# Sheet1.net
KiCad netlist of a schematic drawn in Altium Designer
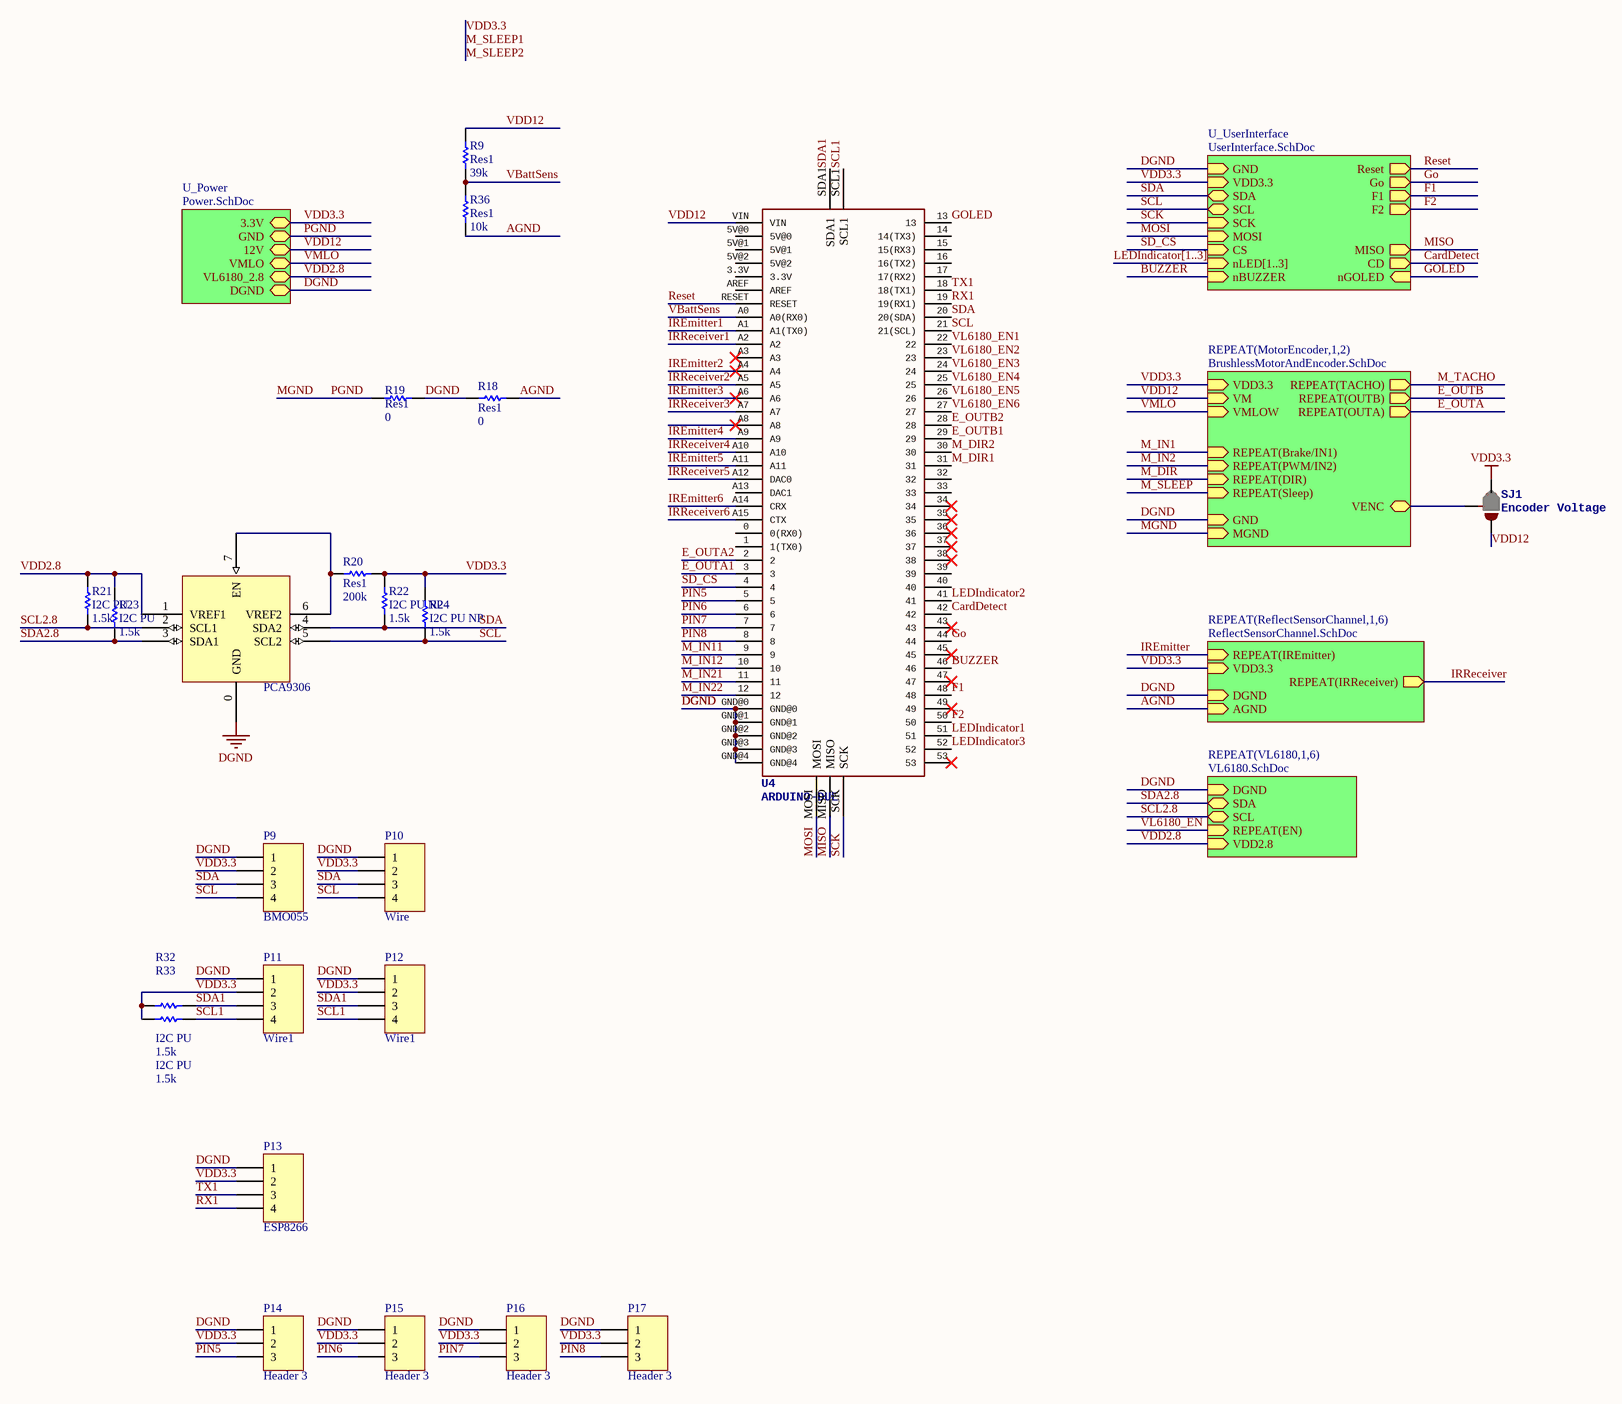
[diagram p0: Sheet1.SchDoc]

(export (version "E")
  (design (tool "Eeschema 10.0.6"))
  (components
    (comp (ref "P9")
      (value "BMO055")
      (footprint "PH_4_PTH")
      (description "Header, 4-Pin")
      (fields (field (name "PUBLISHER") "Altium Limited"))
      (libsource (lib "SmartMouse2016") (part "Header 4"))
    )
    (comp (ref "P10")
      (value "Wire")
      (footprint "PH_4_PTH")
      (description "Header, 4-Pin")
      (fields (field (name "PUBLISHER") "Altium Limited"))
      (libsource (lib "SmartMouse2016") (part "Header 4"))
    )
    (comp (ref "P11")
      (value "Wire1")
      (footprint "PH_4_PTH")
      (description "Header, 4-Pin")
      (fields (field (name "PUBLISHER") "Altium Limited"))
      (libsource (lib "SmartMouse2016") (part "Header 4"))
    )
    (comp (ref "P12")
      (value "Wire1")
      (footprint "PH_4_PTH")
      (description "Header, 4-Pin")
      (fields (field (name "PUBLISHER") "Altium Limited"))
      (libsource (lib "SmartMouse2016") (part "Header 4"))
    )
    (comp (ref "P13")
      (value "ESP8266")
      (footprint "PH_4_PTH")
      (description "Header, 4-Pin")
      (fields (field (name "PUBLISHER") "Altium Limited"))
      (libsource (lib "SmartMouse2016") (part "Header 4"))
    )
    (comp (ref "P14")
      (value "Header 3")
      (footprint "HDR1X3")
      (description "Header, 3-Pin")
      (fields (field (name "PUBLISHER") "Altium Limited"))
      (libsource (lib "Miscellaneous Connectors") (part "Header 3"))
    )
    (comp (ref "P15")
      (value "Header 3")
      (footprint "HDR1X3")
      (description "Header, 3-Pin")
      (fields (field (name "PUBLISHER") "Altium Limited"))
      (libsource (lib "Miscellaneous Connectors") (part "Header 3"))
    )
    (comp (ref "P16")
      (value "Header 3")
      (footprint "HDR1X3")
      (description "Header, 3-Pin")
      (fields (field (name "PUBLISHER") "Altium Limited"))
      (libsource (lib "Miscellaneous Connectors") (part "Header 3"))
    )
    (comp (ref "P17")
      (value "Header 3")
      (footprint "HDR1X3")
      (description "Header, 3-Pin")
      (fields (field (name "PUBLISHER") "Altium Limited"))
      (libsource (lib "Miscellaneous Connectors") (part "Header 3"))
    )
    (comp (ref "PCA1")
      (value "PCA9306")
      (footprint "SOIC_E200_8")
      (description "I2C shifting voltage")
      (libsource (lib "patricklib") (part "Component_1_1"))
    )
    (comp (ref "R9")
      (value "Res1")
      (footprint "RES_0805")
      (description "Resistor")
      (fields (field (name "ALTIUM_VALUE") "39k") (field (name "PUBLISHER") "Altium Limited"))
      (libsource (lib "SmartMouse2016") (part "Res1"))
    )
    (comp (ref "R18")
      (value "Res1")
      (footprint "RES_0805")
      (description "Resistor")
      (fields (field (name "ALTIUM_VALUE") "0") (field (name "PUBLISHER") "Altium Limited"))
      (libsource (lib "SmartMouse2016") (part "Res1"))
    )
    (comp (ref "R19")
      (value "Res1")
      (footprint "RES_0805")
      (description "Resistor")
      (fields (field (name "ALTIUM_VALUE") "0") (field (name "PUBLISHER") "Altium Limited"))
      (libsource (lib "SmartMouse2016") (part "Res1"))
    )
    (comp (ref "R20")
      (value "Res1")
      (footprint "RES_0805")
      (description "Resistor")
      (fields (field (name "ALTIUM_VALUE") "200k") (field (name "PUBLISHER") "Altium Limited"))
      (libsource (lib "SmartMouse2016") (part "Res1"))
    )
    (comp (ref "R21")
      (value "I2C PU")
      (footprint "RES_0805")
      (description "Resistor")
      (fields (field (name "ALTIUM_VALUE") "1.5k") (field (name "PUBLISHER") "Altium Limited"))
      (libsource (lib "SmartMouse2016") (part "Res1"))
    )
    (comp (ref "R22")
      (value "I2C PU NP")
      (footprint "RES_0805")
      (description "Resistor")
      (fields (field (name "ALTIUM_VALUE") "1.5k") (field (name "PUBLISHER") "Altium Limited"))
      (libsource (lib "SmartMouse2016") (part "Res1"))
    )
    (comp (ref "R23")
      (value "I2C PU")
      (footprint "RES_0805")
      (description "Resistor")
      (fields (field (name "ALTIUM_VALUE") "1.5k") (field (name "PUBLISHER") "Altium Limited"))
      (libsource (lib "SmartMouse2016") (part "Res1"))
    )
    (comp (ref "R24")
      (value "I2C PU NP")
      (footprint "RES_0805")
      (description "Resistor")
      (fields (field (name "ALTIUM_VALUE") "1.5k") (field (name "PUBLISHER") "Altium Limited"))
      (libsource (lib "SmartMouse2016") (part "Res1"))
    )
    (comp (ref "R32")
      (value "I2C PU")
      (footprint "RES_0805")
      (description "Resistor")
      (fields (field (name "ALTIUM_VALUE") "1.5k") (field (name "PUBLISHER") "Altium Limited"))
      (libsource (lib "SmartMouse2016") (part "Res1"))
    )
    (comp (ref "R33")
      (value "I2C PU")
      (footprint "RES_0805")
      (description "Resistor")
      (fields (field (name "ALTIUM_VALUE") "1.5k") (field (name "PUBLISHER") "Altium Limited"))
      (libsource (lib "SmartMouse2016") (part "Res1"))
    )
    (comp (ref "R36")
      (value "Res1")
      (footprint "RES_0805")
      (description "Resistor")
      (fields (field (name "ALTIUM_VALUE") "10k") (field (name "PUBLISHER") "Altium Limited"))
      (libsource (lib "SmartMouse2016") (part "Res1"))
    )
    (comp (ref "SJ1")
      (value "Encoder Voltage")
      (footprint "PAD-JUMPER-3-2OF3_NC_BY_PASTE_YES_SILK_FULL_BOX")
      (libsource (lib "SparkFun-Passives") (part "JUMPER-PAD-3-2OF3_NC_BY_PASTE"))
    )
    (comp (ref "U4")
      (value "ARDUINO-DUE")
      (footprint "ARDUINO_DUE")
      (libsource (lib "Robotics") (part "ARDUINO-DUE"))
    )
  )
  (nets
    (net (code "1") (name "/AGND") (class "Default")
      (node (ref "R18") (pin "2") (pinfunction "2_2") (pintype "passive"))
      (node (ref "R36") (pin "1") (pinfunction "1_1") (pintype "passive"))
    )
    (net (code "2") (name "/BUZZER") (class "Default")
      (node (ref "U4") (pin "46") (pinfunction "46_46") (pintype "passive"))
    )
    (net (code "3") (name "/CardDetect") (class "Default")
      (node (ref "U4") (pin "42") (pinfunction "42_42") (pintype "passive"))
    )
    (net (code "5") (name "/E_OUTA1") (class "Default")
      (node (ref "U4") (pin "3") (pinfunction "3_3") (pintype "passive"))
    )
    (net (code "6") (name "/E_OUTA2") (class "Default")
      (node (ref "U4") (pin "2") (pinfunction "2_2") (pintype "passive"))
    )
    (net (code "8") (name "/E_OUTB1") (class "Default")
      (node (ref "U4") (pin "29") (pinfunction "29_29") (pintype "passive"))
    )
    (net (code "9") (name "/E_OUTB2") (class "Default")
      (node (ref "U4") (pin "28") (pinfunction "28_28") (pintype "passive"))
    )
    (net (code "10") (name "/F1") (class "Default")
      (node (ref "U4") (pin "48") (pinfunction "48_48") (pintype "passive"))
    )
    (net (code "11") (name "/F2") (class "Default")
      (node (ref "U4") (pin "50") (pinfunction "50_50") (pintype "passive"))
    )
    (net (code "12") (name "/GOLED") (class "Default")
      (node (ref "U4") (pin "13") (pinfunction "13_13") (pintype "passive"))
    )
    (net (code "13") (name "/Go") (class "Default")
      (node (ref "U4") (pin "44") (pinfunction "44_44") (pintype "passive"))
    )
    (net (code "15") (name "/IREmitter1") (class "Default")
      (node (ref "U4") (pin "A1") (pinfunction "A1(TX0)_A1") (pintype "passive"))
    )
    (net (code "16") (name "/IREmitter2") (class "Default")
      (node (ref "U4") (pin "A4") (pinfunction "A4_A4") (pintype "passive+no_connect"))
    )
    (net (code "17") (name "/IREmitter3") (class "Default")
      (node (ref "U4") (pin "A6") (pinfunction "A6_A6") (pintype "passive+no_connect"))
    )
    (net (code "18") (name "/IREmitter4") (class "Default")
      (node (ref "U4") (pin "A9") (pinfunction "A9_A9") (pintype "passive"))
    )
    (net (code "19") (name "/IREmitter5") (class "Default")
      (node (ref "U4") (pin "A11") (pinfunction "A11_A11") (pintype "passive"))
    )
    (net (code "20") (name "/IREmitter6") (class "Default")
      (node (ref "U4") (pin "A14") (pinfunction "CRX_A14") (pintype "passive"))
    )
    (net (code "22") (name "/IRReceiver1") (class "Default")
      (node (ref "U4") (pin "A2") (pinfunction "A2_A2") (pintype "passive"))
    )
    (net (code "23") (name "/IRReceiver2") (class "Default")
      (node (ref "U4") (pin "A5") (pinfunction "A5_A5") (pintype "passive"))
    )
    (net (code "24") (name "/IRReceiver3") (class "Default")
      (node (ref "U4") (pin "A7") (pinfunction "A7_A7") (pintype "passive"))
    )
    (net (code "25") (name "/IRReceiver4") (class "Default")
      (node (ref "U4") (pin "A10") (pinfunction "A10_A10") (pintype "passive"))
    )
    (net (code "26") (name "/IRReceiver5") (class "Default")
      (node (ref "U4") (pin "A12") (pinfunction "DAC0_A12") (pintype "passive"))
    )
    (net (code "27") (name "/IRReceiver6") (class "Default")
      (node (ref "U4") (pin "A15") (pinfunction "CTX_A15") (pintype "passive"))
    )
    (net (code "28") (name "/LEDIndicator1") (class "Default")
      (node (ref "U4") (pin "51") (pinfunction "51_51") (pintype "passive"))
    )
    (net (code "29") (name "/LEDIndicator2") (class "Default")
      (node (ref "U4") (pin "41") (pinfunction "41_41") (pintype "passive"))
    )
    (net (code "30") (name "/LEDIndicator3") (class "Default")
      (node (ref "U4") (pin "52") (pinfunction "52_52") (pintype "passive"))
    )
    (net (code "32") (name "/MGND") (class "Default")
      (node (ref "R19") (pin "1") (pinfunction "1_1") (pintype "passive"))
    )
    (net (code "33") (name "/MISO") (class "Default")
      (node (ref "U4") (pin "MISO") (pinfunction "MISO_MISO") (pintype "passive"))
    )
    (net (code "34") (name "/MOSI") (class "Default")
      (node (ref "U4") (pin "MOSI") (pinfunction "MOSI_MOSI") (pintype "passive"))
    )
    (net (code "36") (name "/M_DIR1") (class "Default")
      (node (ref "U4") (pin "31") (pinfunction "31_31") (pintype "passive"))
    )
    (net (code "37") (name "/M_DIR2") (class "Default")
      (node (ref "U4") (pin "30") (pinfunction "30_30") (pintype "passive"))
    )
    (net (code "40") (name "/M_IN11") (class "Default")
      (node (ref "U4") (pin "9") (pinfunction "9_9") (pintype "passive"))
    )
    (net (code "41") (name "/M_IN12") (class "Default")
      (node (ref "U4") (pin "10") (pinfunction "10_10") (pintype "passive"))
    )
    (net (code "42") (name "/M_IN21") (class "Default")
      (node (ref "U4") (pin "11") (pinfunction "11_11") (pintype "passive"))
    )
    (net (code "43") (name "/M_IN22") (class "Default")
      (node (ref "U4") (pin "12") (pinfunction "12_12") (pintype "passive"))
    )
    (net (code "46") (name "/PIN5") (class "Default")
      (node (ref "P14") (pin "3") (pinfunction "3_3") (pintype "passive"))
      (node (ref "U4") (pin "5") (pinfunction "5_5") (pintype "passive"))
    )
    (net (code "47") (name "/PIN6") (class "Default")
      (node (ref "P15") (pin "3") (pinfunction "3_3") (pintype "passive"))
      (node (ref "U4") (pin "6") (pinfunction "6_6") (pintype "passive"))
    )
    (net (code "48") (name "/PIN7") (class "Default")
      (node (ref "P16") (pin "3") (pinfunction "3_3") (pintype "passive"))
      (node (ref "U4") (pin "7") (pinfunction "7_7") (pintype "passive"))
    )
    (net (code "49") (name "/PIN8") (class "Default")
      (node (ref "P17") (pin "3") (pinfunction "3_3") (pintype "passive"))
      (node (ref "U4") (pin "8") (pinfunction "8_8") (pintype "passive"))
    )
    (net (code "50") (name "/RX1") (class "Default")
      (node (ref "P13") (pin "4") (pinfunction "4_4") (pintype "passive"))
      (node (ref "U4") (pin "19") (pinfunction "19(RX1)_19") (pintype "passive"))
    )
    (net (code "51") (name "/Reset") (class "Default")
      (node (ref "U4") (pin "RESET") (pinfunction "RESET_RESET") (pintype "passive"))
    )
    (net (code "52") (name "/SCK") (class "Default")
      (node (ref "U4") (pin "SCK") (pinfunction "SCK_SCK") (pintype "passive"))
    )
    (net (code "53") (name "/SCL") (class "Default")
      (node (ref "P10") (pin "4") (pinfunction "4_4") (pintype "passive"))
      (node (ref "P9") (pin "4") (pinfunction "4_4") (pintype "passive"))
      (node (ref "PCA1") (pin "5") (pinfunction "SCL2_5") (pintype "bidirectional"))
      (node (ref "R24") (pin "1") (pinfunction "1_1") (pintype "passive"))
      (node (ref "U4") (pin "21") (pinfunction "21(SCL)_21") (pintype "passive"))
    )
    (net (code "54") (name "/SCL1") (class "Default")
      (node (ref "P11") (pin "4") (pinfunction "4_4") (pintype "passive"))
      (node (ref "P12") (pin "4") (pinfunction "4_4") (pintype "passive"))
      (node (ref "R33") (pin "2") (pinfunction "2_2") (pintype "passive"))
      (node (ref "U4") (pin "SCL1") (pinfunction "SCL1_SCL1") (pintype "passive"))
    )
    (net (code "55") (name "/SCL2.8") (class "Default")
      (node (ref "PCA1") (pin "2") (pinfunction "SCL1_2") (pintype "bidirectional"))
      (node (ref "R21") (pin "1") (pinfunction "1_1") (pintype "passive"))
    )
    (net (code "56") (name "/SDA") (class "Default")
      (node (ref "P10") (pin "3") (pinfunction "3_3") (pintype "passive"))
      (node (ref "P9") (pin "3") (pinfunction "3_3") (pintype "passive"))
      (node (ref "PCA1") (pin "4") (pinfunction "SDA2_4") (pintype "bidirectional"))
      (node (ref "R22") (pin "1") (pinfunction "1_1") (pintype "passive"))
      (node (ref "U4") (pin "20") (pinfunction "20(SDA)_20") (pintype "passive"))
    )
    (net (code "57") (name "/SDA1") (class "Default")
      (node (ref "P11") (pin "3") (pinfunction "3_3") (pintype "passive"))
      (node (ref "P12") (pin "3") (pinfunction "3_3") (pintype "passive"))
      (node (ref "R32") (pin "2") (pinfunction "2_2") (pintype "passive"))
      (node (ref "U4") (pin "SDA1") (pinfunction "SDA1_SDA1") (pintype "passive"))
    )
    (net (code "58") (name "/SDA2.8") (class "Default")
      (node (ref "PCA1") (pin "3") (pinfunction "SDA1_3") (pintype "bidirectional"))
      (node (ref "R23") (pin "1") (pinfunction "1_1") (pintype "passive"))
    )
    (net (code "59") (name "/SD_CS") (class "Default")
      (node (ref "U4") (pin "4") (pinfunction "4_4") (pintype "passive"))
    )
    (net (code "60") (name "/TX1") (class "Default")
      (node (ref "P13") (pin "3") (pinfunction "3_3") (pintype "passive"))
      (node (ref "U4") (pin "18") (pinfunction "18(TX1)_18") (pintype "passive"))
    )
    (net (code "61") (name "/VBattSens") (class "Default")
      (node (ref "R36") (pin "2") (pinfunction "2_2") (pintype "passive"))
      (node (ref "R9") (pin "1") (pinfunction "1_1") (pintype "passive"))
      (node (ref "U4") (pin "A0") (pinfunction "A0(RX0)_A0") (pintype "passive"))
    )
    (net (code "62") (name "/VDD2.8") (class "Default")
      (node (ref "PCA1") (pin "1") (pinfunction "VREF1_1") (pintype "power_in"))
      (node (ref "R21") (pin "2") (pinfunction "2_2") (pintype "passive"))
      (node (ref "R23") (pin "2") (pinfunction "2_2") (pintype "passive"))
    )
    (net (code "63") (name "/VDD12") (class "Default")
      (node (ref "R9") (pin "2") (pinfunction "2_2") (pintype "passive"))
      (node (ref "SJ1") (pin "1") (pinfunction "1_1") (pintype "passive"))
      (node (ref "U4") (pin "VIN") (pinfunction "VIN_VIN") (pintype "passive"))
    )
    (net (code "64") (name "/VENC") (class "Default")
      (node (ref "SJ1") (pin "2") (pinfunction "2_2") (pintype "passive"))
    )
    (net (code "66") (name "/VL6180_EN1") (class "Default")
      (node (ref "U4") (pin "22") (pinfunction "22_22") (pintype "passive"))
    )
    (net (code "67") (name "/VL6180_EN2") (class "Default")
      (node (ref "U4") (pin "23") (pinfunction "23_23") (pintype "passive"))
    )
    (net (code "68") (name "/VL6180_EN3") (class "Default")
      (node (ref "U4") (pin "24") (pinfunction "24_24") (pintype "passive"))
    )
    (net (code "69") (name "/VL6180_EN4") (class "Default")
      (node (ref "U4") (pin "25") (pinfunction "25_25") (pintype "passive"))
    )
    (net (code "70") (name "/VL6180_EN5") (class "Default")
      (node (ref "U4") (pin "26") (pinfunction "26_26") (pintype "passive"))
    )
    (net (code "71") (name "/VL6180_EN6") (class "Default")
      (node (ref "U4") (pin "27") (pinfunction "27_27") (pintype "passive"))
    )
    (net (code "73") (name "DGND") (class "Default")
      (node (ref "P10") (pin "1") (pinfunction "1_1") (pintype "passive"))
      (node (ref "P11") (pin "1") (pinfunction "1_1") (pintype "passive"))
      (node (ref "P12") (pin "1") (pinfunction "1_1") (pintype "passive"))
      (node (ref "P13") (pin "1") (pinfunction "1_1") (pintype "passive"))
      (node (ref "P14") (pin "1") (pinfunction "1_1") (pintype "passive"))
      (node (ref "P15") (pin "1") (pinfunction "1_1") (pintype "passive"))
      (node (ref "P16") (pin "1") (pinfunction "1_1") (pintype "passive"))
      (node (ref "P17") (pin "1") (pinfunction "1_1") (pintype "passive"))
      (node (ref "P9") (pin "1") (pinfunction "1_1") (pintype "passive"))
      (node (ref "PCA1") (pin "0") (pinfunction "GND_0") (pintype "power_in"))
      (node (ref "R18") (pin "1") (pinfunction "1_1") (pintype "passive"))
      (node (ref "R19") (pin "2") (pinfunction "2_2") (pintype "passive"))
      (node (ref "U4") (pin "GND@0") (pinfunction "GND@0_GND@0") (pintype "passive"))
      (node (ref "U4") (pin "GND@1") (pinfunction "GND@1_GND@1") (pintype "passive"))
      (node (ref "U4") (pin "GND@2") (pinfunction "GND@2_GND@2") (pintype "passive"))
      (node (ref "U4") (pin "GND@3") (pinfunction "GND@3_GND@3") (pintype "passive"))
      (node (ref "U4") (pin "GND@4") (pinfunction "GND@4_GND@4") (pintype "passive"))
    )
    (net (code "74") (name "Net-(PCA1-EN)") (class "Default")
      (node (ref "PCA1") (pin "6") (pinfunction "VREF2_6") (pintype "power_in"))
      (node (ref "PCA1") (pin "7") (pinfunction "EN_7") (pintype "input"))
      (node (ref "R20") (pin "1") (pinfunction "1_1") (pintype "passive"))
    )
    (net (code "75") (name "VDD3.3") (class "Default")
      (node (ref "P10") (pin "2") (pinfunction "2_2") (pintype "passive"))
      (node (ref "P11") (pin "2") (pinfunction "2_2") (pintype "passive"))
      (node (ref "P12") (pin "2") (pinfunction "2_2") (pintype "passive"))
      (node (ref "P13") (pin "2") (pinfunction "2_2") (pintype "passive"))
      (node (ref "P14") (pin "2") (pinfunction "2_2") (pintype "passive"))
      (node (ref "P15") (pin "2") (pinfunction "2_2") (pintype "passive"))
      (node (ref "P16") (pin "2") (pinfunction "2_2") (pintype "passive"))
      (node (ref "P17") (pin "2") (pinfunction "2_2") (pintype "passive"))
      (node (ref "P9") (pin "2") (pinfunction "2_2") (pintype "passive"))
      (node (ref "R20") (pin "2") (pinfunction "2_2") (pintype "passive"))
      (node (ref "R22") (pin "2") (pinfunction "2_2") (pintype "passive"))
      (node (ref "R24") (pin "2") (pinfunction "2_2") (pintype "passive"))
      (node (ref "R32") (pin "1") (pinfunction "1_1") (pintype "passive"))
      (node (ref "R33") (pin "1") (pinfunction "1_1") (pintype "passive"))
      (node (ref "SJ1") (pin "3") (pinfunction "3_3") (pintype "passive"))
    )
    (net (code "76") (name "unconnected-(U4-0(RX0)-Pad0)") (class "Default")
      (node (ref "U4") (pin "0") (pinfunction "0(RX0)_0") (pintype "passive"))
    )
    (net (code "77") (name "unconnected-(U4-1(TX0)-Pad1)") (class "Default")
      (node (ref "U4") (pin "1") (pinfunction "1(TX0)_1") (pintype "passive"))
    )
    (net (code "78") (name "unconnected-(U4-14(TX3)-Pad14)") (class "Default")
      (node (ref "U4") (pin "14") (pinfunction "14(TX3)_14") (pintype "passive"))
    )
    (net (code "79") (name "unconnected-(U4-15(RX3)-Pad15)") (class "Default")
      (node (ref "U4") (pin "15") (pinfunction "15(RX3)_15") (pintype "passive"))
    )
    (net (code "80") (name "unconnected-(U4-16(TX2)-Pad16)") (class "Default")
      (node (ref "U4") (pin "16") (pinfunction "16(TX2)_16") (pintype "passive"))
    )
    (net (code "81") (name "unconnected-(U4-17(RX2)-Pad17)") (class "Default")
      (node (ref "U4") (pin "17") (pinfunction "17(RX2)_17") (pintype "passive"))
    )
    (net (code "82") (name "unconnected-(U4-DAC1-PadA13)") (class "Default")
      (node (ref "U4") (pin "A13") (pinfunction "DAC1_A13") (pintype "passive"))
    )
    (net (code "83") (name "unconnected-(U4-Pad3.3V)") (class "Default")
      (node (ref "U4") (pin "3.3V") (pinfunction "3.3V_3.3V") (pintype "passive"))
    )
    (net (code "84") (name "unconnected-(U4-Pad5V@0)") (class "Default")
      (node (ref "U4") (pin "5V@0") (pinfunction "5V@0_5V@0") (pintype "passive"))
    )
    (net (code "85") (name "unconnected-(U4-Pad5V@1)") (class "Default")
      (node (ref "U4") (pin "5V@1") (pinfunction "5V@1_5V@1") (pintype "passive"))
    )
    (net (code "86") (name "unconnected-(U4-Pad5V@2)") (class "Default")
      (node (ref "U4") (pin "5V@2") (pinfunction "5V@2_5V@2") (pintype "passive"))
    )
    (net (code "87") (name "unconnected-(U4-Pad32)") (class "Default")
      (node (ref "U4") (pin "32") (pinfunction "32_32") (pintype "passive"))
    )
    (net (code "88") (name "unconnected-(U4-Pad33)") (class "Default")
      (node (ref "U4") (pin "33") (pinfunction "33_33") (pintype "passive"))
    )
    (net (code "89") (name "unconnected-(U4-Pad34)") (class "Default")
      (node (ref "U4") (pin "34") (pinfunction "34_34") (pintype "passive+no_connect"))
    )
    (net (code "90") (name "unconnected-(U4-Pad35)") (class "Default")
      (node (ref "U4") (pin "35") (pinfunction "35_35") (pintype "passive+no_connect"))
    )
    (net (code "91") (name "unconnected-(U4-Pad36)") (class "Default")
      (node (ref "U4") (pin "36") (pinfunction "36_36") (pintype "passive+no_connect"))
    )
    (net (code "92") (name "unconnected-(U4-Pad37)") (class "Default")
      (node (ref "U4") (pin "37") (pinfunction "37_37") (pintype "passive+no_connect"))
    )
    (net (code "93") (name "unconnected-(U4-Pad38)") (class "Default")
      (node (ref "U4") (pin "38") (pinfunction "38_38") (pintype "passive+no_connect"))
    )
    (net (code "94") (name "unconnected-(U4-Pad39)") (class "Default")
      (node (ref "U4") (pin "39") (pinfunction "39_39") (pintype "passive"))
    )
    (net (code "95") (name "unconnected-(U4-Pad40)") (class "Default")
      (node (ref "U4") (pin "40") (pinfunction "40_40") (pintype "passive"))
    )
    (net (code "96") (name "unconnected-(U4-Pad43)") (class "Default")
      (node (ref "U4") (pin "43") (pinfunction "43_43") (pintype "passive+no_connect"))
    )
    (net (code "97") (name "unconnected-(U4-Pad45)") (class "Default")
      (node (ref "U4") (pin "45") (pinfunction "45_45") (pintype "passive+no_connect"))
    )
    (net (code "98") (name "unconnected-(U4-Pad47)") (class "Default")
      (node (ref "U4") (pin "47") (pinfunction "47_47") (pintype "passive+no_connect"))
    )
    (net (code "99") (name "unconnected-(U4-Pad49)") (class "Default")
      (node (ref "U4") (pin "49") (pinfunction "49_49") (pintype "passive+no_connect"))
    )
    (net (code "100") (name "unconnected-(U4-Pad53)") (class "Default")
      (node (ref "U4") (pin "53") (pinfunction "53_53") (pintype "passive+no_connect"))
    )
    (net (code "101") (name "unconnected-(U4-PadA3)") (class "Default")
      (node (ref "U4") (pin "A3") (pinfunction "A3_A3") (pintype "passive+no_connect"))
    )
    (net (code "102") (name "unconnected-(U4-PadA8)") (class "Default")
      (node (ref "U4") (pin "A8") (pinfunction "A8_A8") (pintype "passive+no_connect"))
    )
    (net (code "103") (name "unconnected-(U4-PadAREF)") (class "Default")
      (node (ref "U4") (pin "AREF") (pinfunction "AREF_AREF") (pintype "passive"))
    )
  )
)
